# breakboard.net
KiCad netlist of a schematic drawn in EAGLE
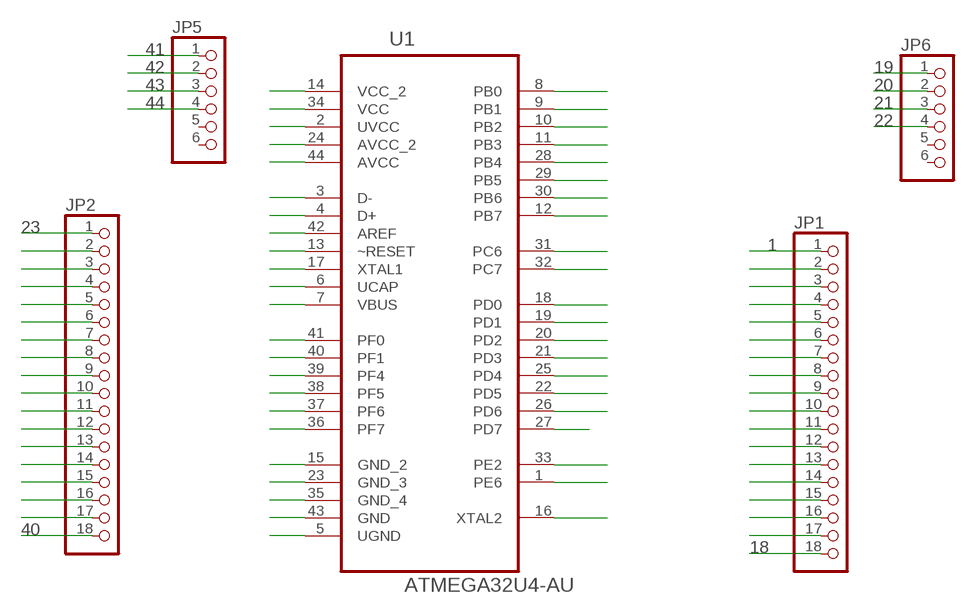
[diagram p0: schematic, sheet 1]

(export (version "E")
  (design (tool "Eeschema 10.0.6"))
  (components
    (comp (ref "JP1")
      (value "PINHD-1X18-BIG")
      (footprint "eagle-import:1X18-BIG")
      (libsource (lib "eagle-import") (part "PINHD-1X18-BIG"))
    )
    (comp (ref "JP2")
      (value "PINHD-1X18-BIG")
      (footprint "eagle-import:1X18-BIG")
      (libsource (lib "eagle-import") (part "PINHD-1X18-BIG"))
    )
    (comp (ref "JP5")
      (value "PINHD-1X6")
      (footprint "eagle-import:1X06")
      (libsource (lib "eagle-import") (part "PINHD-1X6"))
    )
    (comp (ref "JP6")
      (value "PINHD-1X6")
      (footprint "eagle-import:1X06")
      (libsource (lib "eagle-import") (part "PINHD-1X6"))
    )
    (comp (ref "U1")
      (value "ATMEGA32U4-AU")
      (footprint "eagle-import:QFP80P1200X1200X120-44N")
      (libsource (lib "eagle-import") (part "ATMEGA32U4-AU"))
    )
  )
  (nets
    (net (code "1") (name "/1") (class "Default")
      (node (ref "JP1") (pin "1") (pinfunction "1_1") (pintype "passive"))
      (node (ref "U1") (pin "1") (pinfunction "PE6_1") (pintype "bidirectional"))
    )
    (net (code "2") (name "/2") (class "Default")
      (node (ref "JP1") (pin "2") (pinfunction "2_2") (pintype "passive"))
      (node (ref "U1") (pin "2") (pinfunction "UVCC_2") (pintype "power_in"))
    )
    (net (code "3") (name "/3") (class "Default")
      (node (ref "JP1") (pin "3") (pinfunction "3_3") (pintype "passive"))
      (node (ref "U1") (pin "3") (pinfunction "D-_3") (pintype "passive"))
    )
    (net (code "4") (name "/4") (class "Default")
      (node (ref "JP1") (pin "4") (pinfunction "4_4") (pintype "passive"))
      (node (ref "U1") (pin "4") (pinfunction "D+_4") (pintype "passive"))
    )
    (net (code "5") (name "/5") (class "Default")
      (node (ref "JP1") (pin "5") (pinfunction "5_5") (pintype "passive"))
      (node (ref "U1") (pin "5") (pinfunction "UGND_5") (pintype "passive"))
    )
    (net (code "6") (name "/6") (class "Default")
      (node (ref "JP1") (pin "6") (pinfunction "6_6") (pintype "passive"))
      (node (ref "U1") (pin "6") (pinfunction "UCAP_6") (pintype "power_in"))
    )
    (net (code "7") (name "/7") (class "Default")
      (node (ref "JP1") (pin "7") (pinfunction "7_7") (pintype "passive"))
      (node (ref "U1") (pin "7") (pinfunction "VBUS_7") (pintype "input"))
    )
    (net (code "8") (name "/8") (class "Default")
      (node (ref "JP1") (pin "8") (pinfunction "8_8") (pintype "passive"))
      (node (ref "U1") (pin "8") (pinfunction "PB0_8") (pintype "bidirectional"))
    )
    (net (code "9") (name "/9") (class "Default")
      (node (ref "JP1") (pin "9") (pinfunction "9_9") (pintype "passive"))
      (node (ref "U1") (pin "9") (pinfunction "PB1_9") (pintype "bidirectional"))
    )
    (net (code "10") (name "/10") (class "Default")
      (node (ref "JP1") (pin "10") (pinfunction "10_10") (pintype "passive"))
      (node (ref "U1") (pin "10") (pinfunction "PB2_10") (pintype "bidirectional"))
    )
    (net (code "11") (name "/11") (class "Default")
      (node (ref "JP1") (pin "11") (pinfunction "11_11") (pintype "passive"))
      (node (ref "U1") (pin "11") (pinfunction "PB3_11") (pintype "bidirectional"))
    )
    (net (code "12") (name "/12") (class "Default")
      (node (ref "JP1") (pin "12") (pinfunction "12_12") (pintype "passive"))
      (node (ref "U1") (pin "12") (pinfunction "PB7_12") (pintype "bidirectional"))
    )
    (net (code "13") (name "/13") (class "Default")
      (node (ref "JP1") (pin "13") (pinfunction "13_13") (pintype "passive"))
      (node (ref "U1") (pin "13") (pinfunction "~{RESET}_13") (pintype "input"))
    )
    (net (code "14") (name "/14") (class "Default")
      (node (ref "JP1") (pin "14") (pinfunction "14_14") (pintype "passive"))
      (node (ref "U1") (pin "14") (pinfunction "VCC_2_14") (pintype "power_in"))
    )
    (net (code "15") (name "/15") (class "Default")
      (node (ref "JP1") (pin "15") (pinfunction "15_15") (pintype "passive"))
      (node (ref "U1") (pin "15") (pinfunction "GND_2_15") (pintype "passive"))
    )
    (net (code "16") (name "/16") (class "Default")
      (node (ref "JP1") (pin "16") (pinfunction "16_16") (pintype "passive"))
      (node (ref "U1") (pin "16") (pinfunction "XTAL2_16") (pintype "output"))
    )
    (net (code "17") (name "/17") (class "Default")
      (node (ref "JP1") (pin "17") (pinfunction "17_17") (pintype "passive"))
      (node (ref "U1") (pin "17") (pinfunction "XTAL1_17") (pintype "input"))
    )
    (net (code "18") (name "/18") (class "Default")
      (node (ref "JP1") (pin "18") (pinfunction "18_18") (pintype "passive"))
      (node (ref "U1") (pin "18") (pinfunction "PD0_18") (pintype "bidirectional"))
    )
    (net (code "19") (name "/19") (class "Default")
      (node (ref "JP6") (pin "1") (pinfunction "1_1") (pintype "passive"))
      (node (ref "U1") (pin "19") (pinfunction "PD1_19") (pintype "bidirectional"))
    )
    (net (code "20") (name "/20") (class "Default")
      (node (ref "JP6") (pin "2") (pinfunction "2_2") (pintype "passive"))
      (node (ref "U1") (pin "20") (pinfunction "PD2_20") (pintype "bidirectional"))
    )
    (net (code "21") (name "/21") (class "Default")
      (node (ref "JP6") (pin "3") (pinfunction "3_3") (pintype "passive"))
      (node (ref "U1") (pin "21") (pinfunction "PD3_21") (pintype "bidirectional"))
    )
    (net (code "22") (name "/22") (class "Default")
      (node (ref "JP6") (pin "4") (pinfunction "4_4") (pintype "passive"))
      (node (ref "U1") (pin "22") (pinfunction "PD5_22") (pintype "bidirectional"))
    )
    (net (code "23") (name "/23") (class "Default")
      (node (ref "JP2") (pin "1") (pinfunction "1_1") (pintype "passive"))
      (node (ref "U1") (pin "23") (pinfunction "GND_3_23") (pintype "passive"))
    )
    (net (code "24") (name "/24") (class "Default")
      (node (ref "JP2") (pin "2") (pinfunction "2_2") (pintype "passive"))
      (node (ref "U1") (pin "24") (pinfunction "AVCC_2_24") (pintype "power_in"))
    )
    (net (code "25") (name "/25") (class "Default")
      (node (ref "JP2") (pin "3") (pinfunction "3_3") (pintype "passive"))
      (node (ref "U1") (pin "25") (pinfunction "PD4_25") (pintype "bidirectional"))
    )
    (net (code "26") (name "/26") (class "Default")
      (node (ref "JP2") (pin "4") (pinfunction "4_4") (pintype "passive"))
      (node (ref "U1") (pin "26") (pinfunction "PD6_26") (pintype "bidirectional"))
    )
    (net (code "27") (name "/27") (class "Default")
      (node (ref "JP2") (pin "5") (pinfunction "5_5") (pintype "passive"))
      (node (ref "U1") (pin "27") (pinfunction "PD7_27") (pintype "bidirectional"))
    )
    (net (code "28") (name "/28") (class "Default")
      (node (ref "JP2") (pin "6") (pinfunction "6_6") (pintype "passive"))
      (node (ref "U1") (pin "28") (pinfunction "PB4_28") (pintype "bidirectional"))
    )
    (net (code "29") (name "/29") (class "Default")
      (node (ref "JP2") (pin "7") (pinfunction "7_7") (pintype "passive"))
      (node (ref "U1") (pin "29") (pinfunction "PB5_29") (pintype "bidirectional"))
    )
    (net (code "30") (name "/30") (class "Default")
      (node (ref "JP2") (pin "8") (pinfunction "8_8") (pintype "passive"))
      (node (ref "U1") (pin "30") (pinfunction "PB6_30") (pintype "bidirectional"))
    )
    (net (code "31") (name "/31") (class "Default")
      (node (ref "JP2") (pin "9") (pinfunction "9_9") (pintype "passive"))
      (node (ref "U1") (pin "31") (pinfunction "PC6_31") (pintype "bidirectional"))
    )
    (net (code "32") (name "/32") (class "Default")
      (node (ref "JP2") (pin "10") (pinfunction "10_10") (pintype "passive"))
      (node (ref "U1") (pin "32") (pinfunction "PC7_32") (pintype "bidirectional"))
    )
    (net (code "33") (name "/33") (class "Default")
      (node (ref "JP2") (pin "11") (pinfunction "11_11") (pintype "passive"))
      (node (ref "U1") (pin "33") (pinfunction "PE2_33") (pintype "bidirectional"))
    )
    (net (code "34") (name "/34") (class "Default")
      (node (ref "JP2") (pin "12") (pinfunction "12_12") (pintype "passive"))
      (node (ref "U1") (pin "34") (pinfunction "VCC_34") (pintype "power_in"))
    )
    (net (code "35") (name "/35") (class "Default")
      (node (ref "JP2") (pin "13") (pinfunction "13_13") (pintype "passive"))
      (node (ref "U1") (pin "35") (pinfunction "GND_4_35") (pintype "passive"))
    )
    (net (code "36") (name "/36") (class "Default")
      (node (ref "JP2") (pin "14") (pinfunction "14_14") (pintype "passive"))
      (node (ref "U1") (pin "36") (pinfunction "PF7_36") (pintype "bidirectional"))
    )
    (net (code "37") (name "/37") (class "Default")
      (node (ref "JP2") (pin "15") (pinfunction "15_15") (pintype "passive"))
      (node (ref "U1") (pin "37") (pinfunction "PF6_37") (pintype "bidirectional"))
    )
    (net (code "38") (name "/38") (class "Default")
      (node (ref "JP2") (pin "16") (pinfunction "16_16") (pintype "passive"))
      (node (ref "U1") (pin "38") (pinfunction "PF5_38") (pintype "bidirectional"))
    )
    (net (code "39") (name "/39") (class "Default")
      (node (ref "JP2") (pin "17") (pinfunction "17_17") (pintype "passive"))
      (node (ref "U1") (pin "39") (pinfunction "PF4_39") (pintype "bidirectional"))
    )
    (net (code "40") (name "/40") (class "Default")
      (node (ref "JP2") (pin "18") (pinfunction "18_18") (pintype "passive"))
      (node (ref "U1") (pin "40") (pinfunction "PF1_40") (pintype "bidirectional"))
    )
    (net (code "41") (name "/41") (class "Default")
      (node (ref "JP5") (pin "1") (pinfunction "1_1") (pintype "passive"))
      (node (ref "U1") (pin "41") (pinfunction "PF0_41") (pintype "bidirectional"))
    )
    (net (code "42") (name "/42") (class "Default")
      (node (ref "JP5") (pin "2") (pinfunction "2_2") (pintype "passive"))
      (node (ref "U1") (pin "42") (pinfunction "AREF_42") (pintype "input"))
    )
    (net (code "43") (name "/43") (class "Default")
      (node (ref "JP5") (pin "3") (pinfunction "3_3") (pintype "passive"))
      (node (ref "U1") (pin "43") (pinfunction "GND_43") (pintype "passive"))
    )
    (net (code "44") (name "/44") (class "Default")
      (node (ref "JP5") (pin "4") (pinfunction "4_4") (pintype "passive"))
      (node (ref "U1") (pin "44") (pinfunction "AVCC_44") (pintype "power_in"))
    )
    (net (code "45") (name "unconnected-(JP5-Pad5)") (class "Default")
      (node (ref "JP5") (pin "5") (pinfunction "5_5") (pintype "passive"))
    )
    (net (code "46") (name "unconnected-(JP5-Pad6)") (class "Default")
      (node (ref "JP5") (pin "6") (pinfunction "6_6") (pintype "passive"))
    )
    (net (code "47") (name "unconnected-(JP6-Pad5)") (class "Default")
      (node (ref "JP6") (pin "5") (pinfunction "5_5") (pintype "passive"))
    )
    (net (code "48") (name "unconnected-(JP6-Pad6)") (class "Default")
      (node (ref "JP6") (pin "6") (pinfunction "6_6") (pintype "passive"))
    )
  )
)
